# kinks.net
KiCad netlist of a schematic drawn in EAGLE
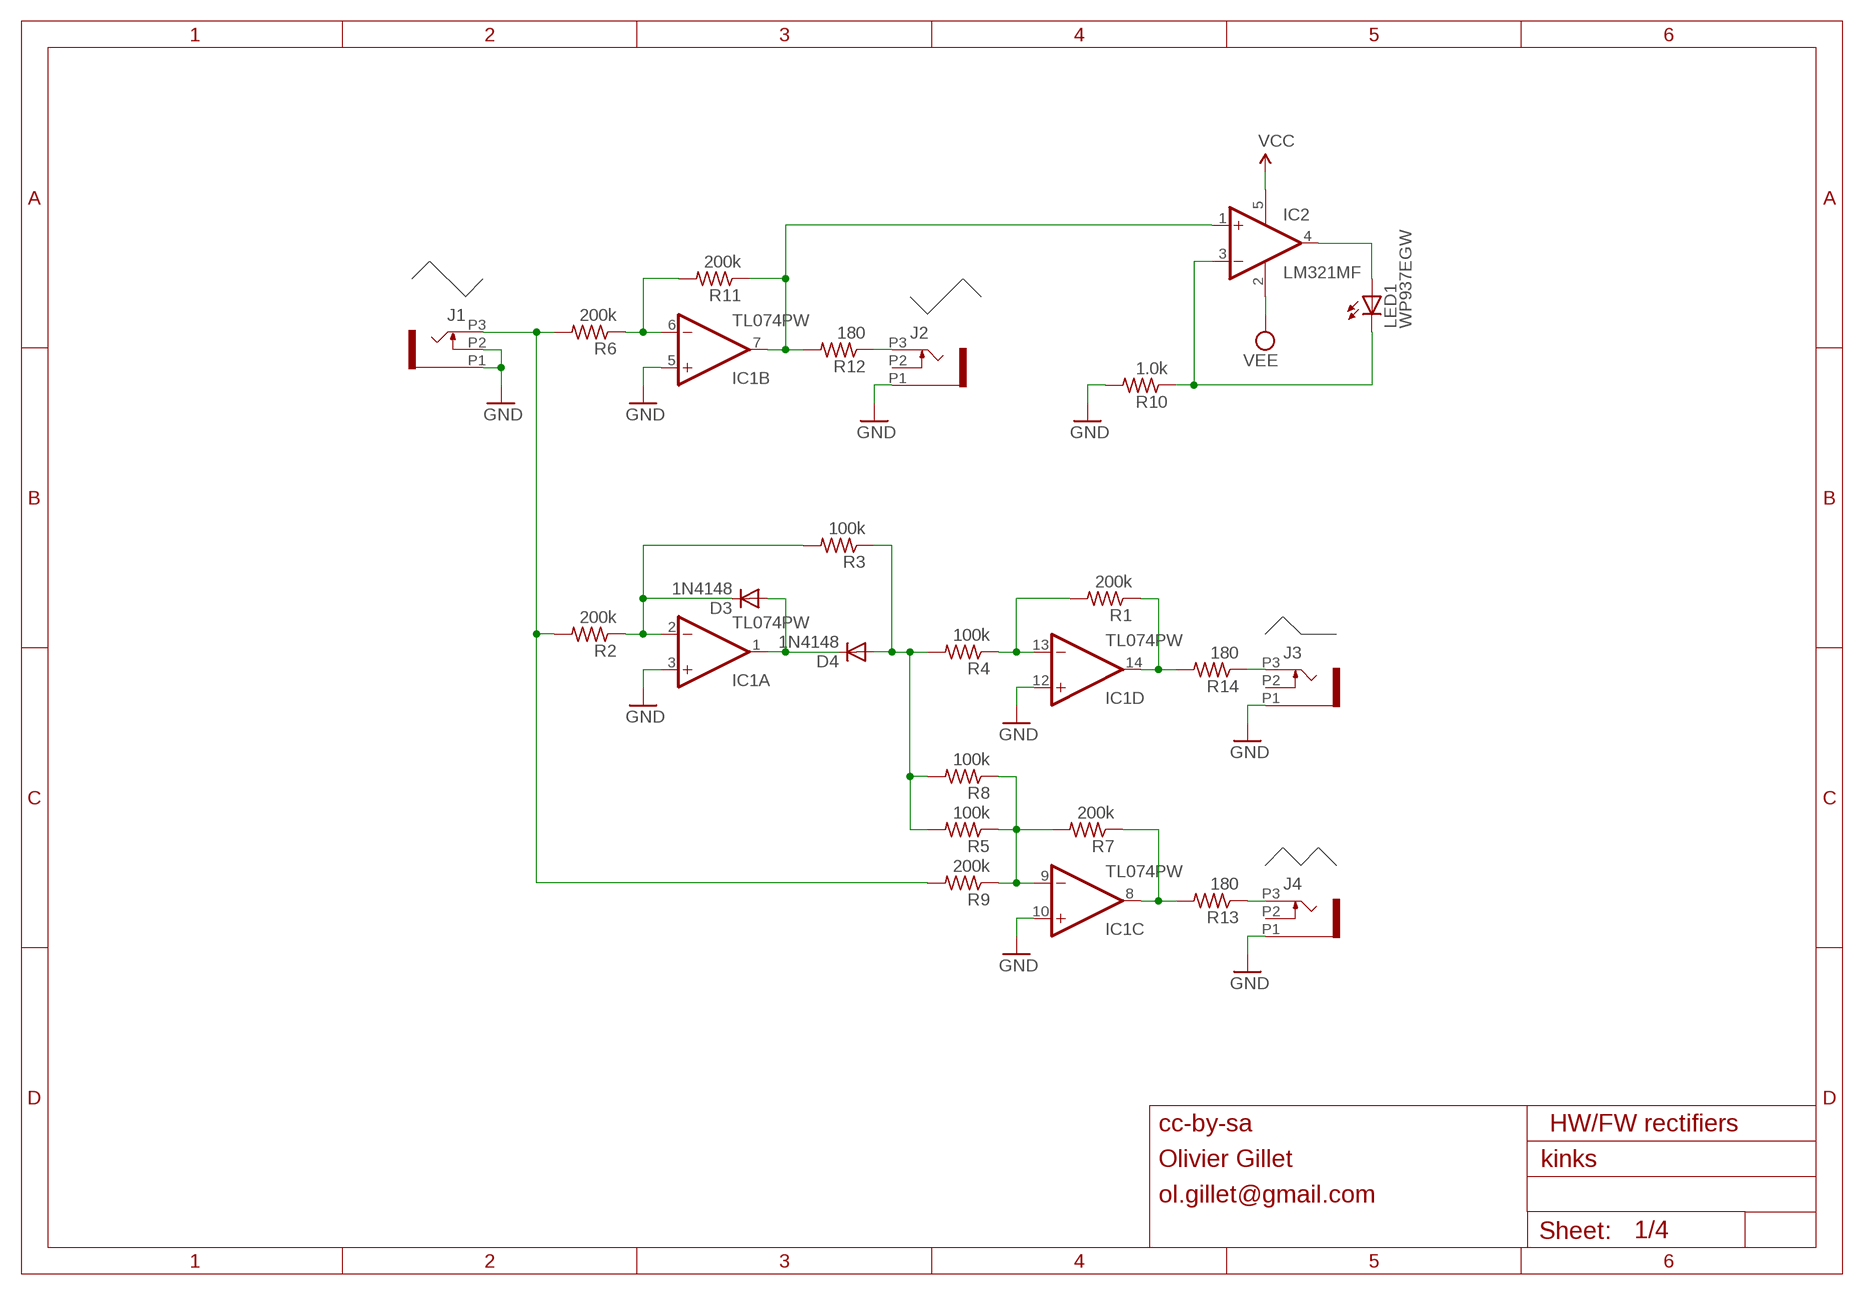
[diagram p0: schematic, sheet 1]
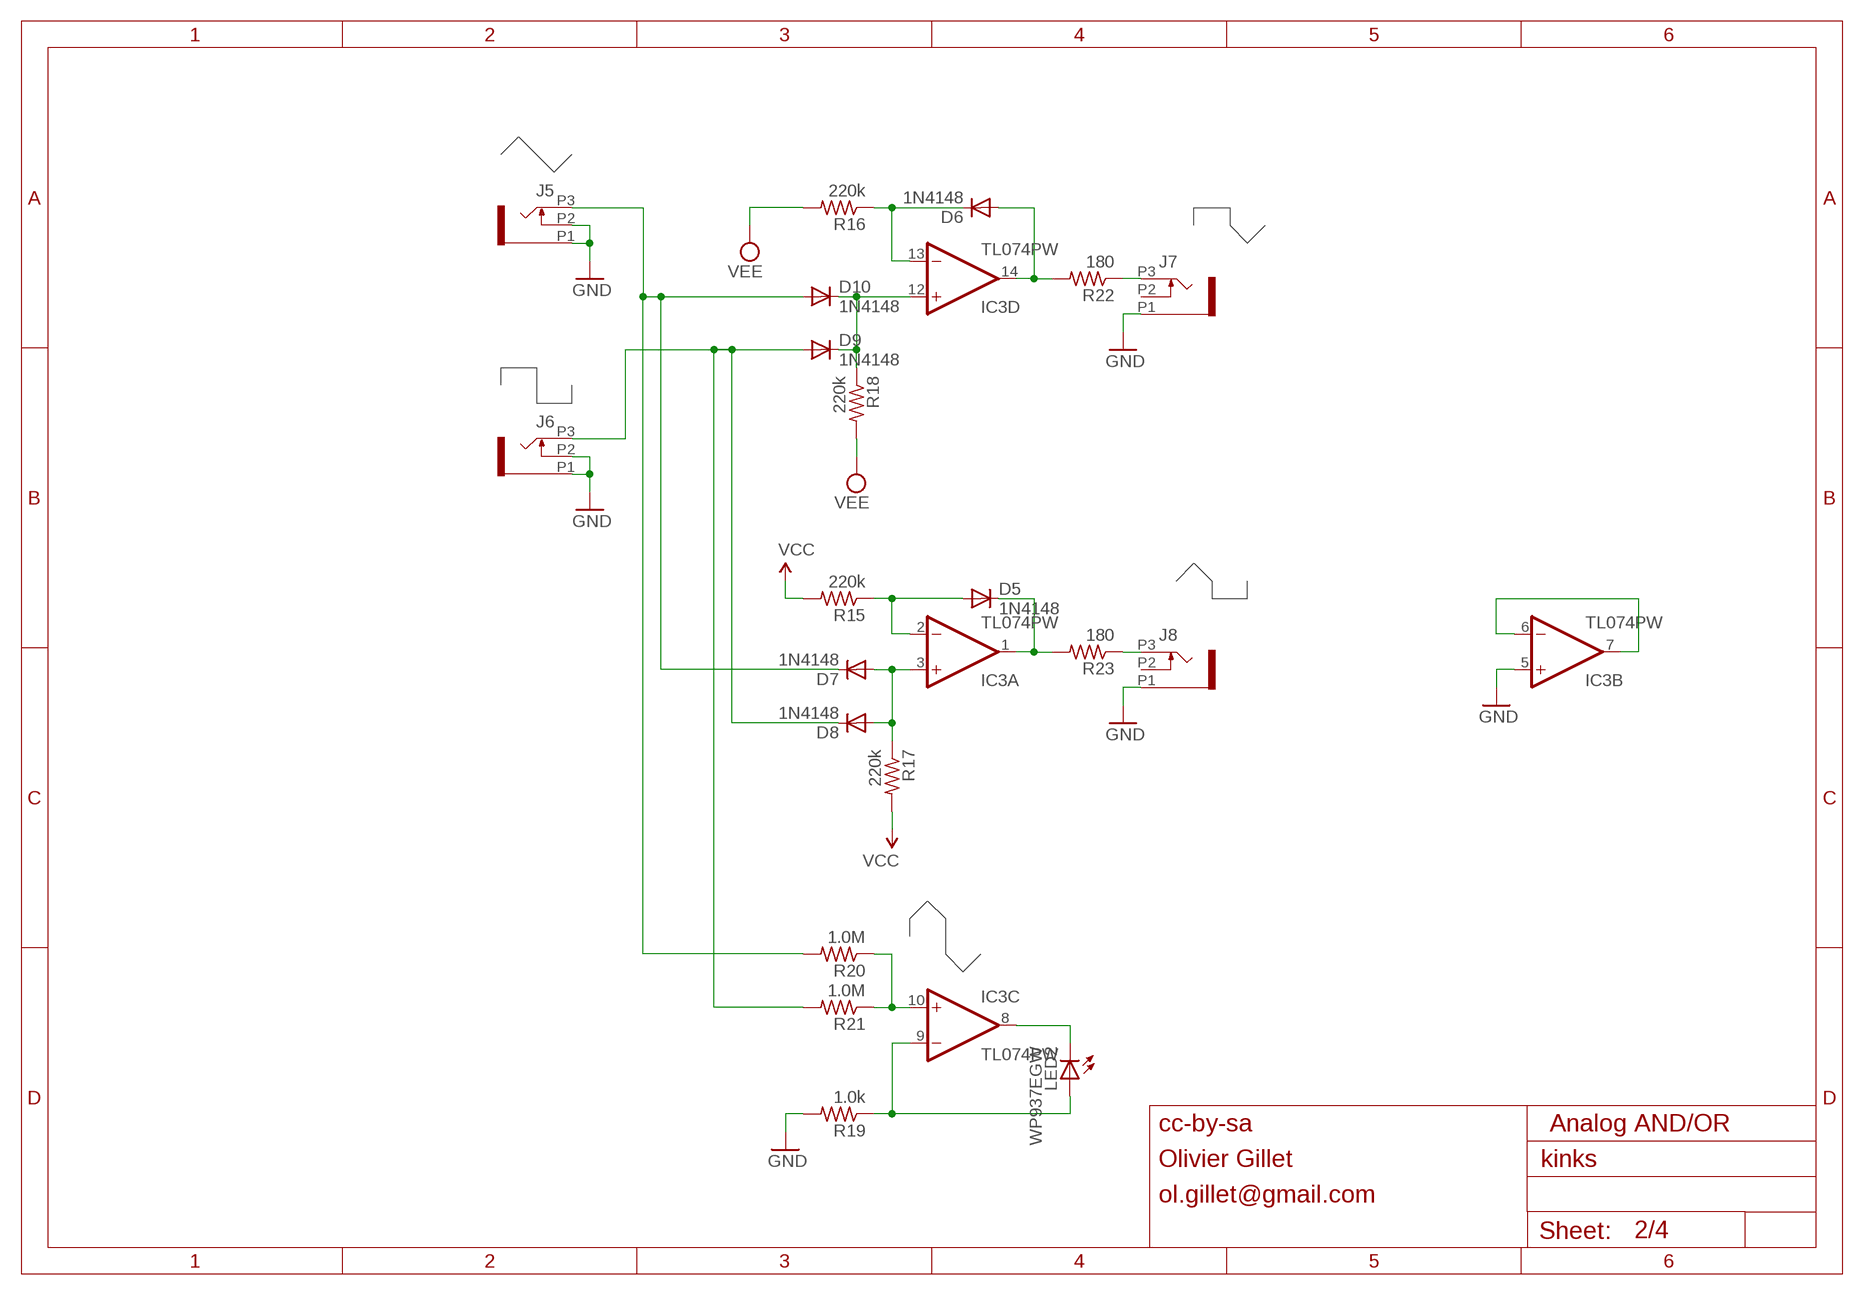
[diagram p1: schematic, sheet 2]
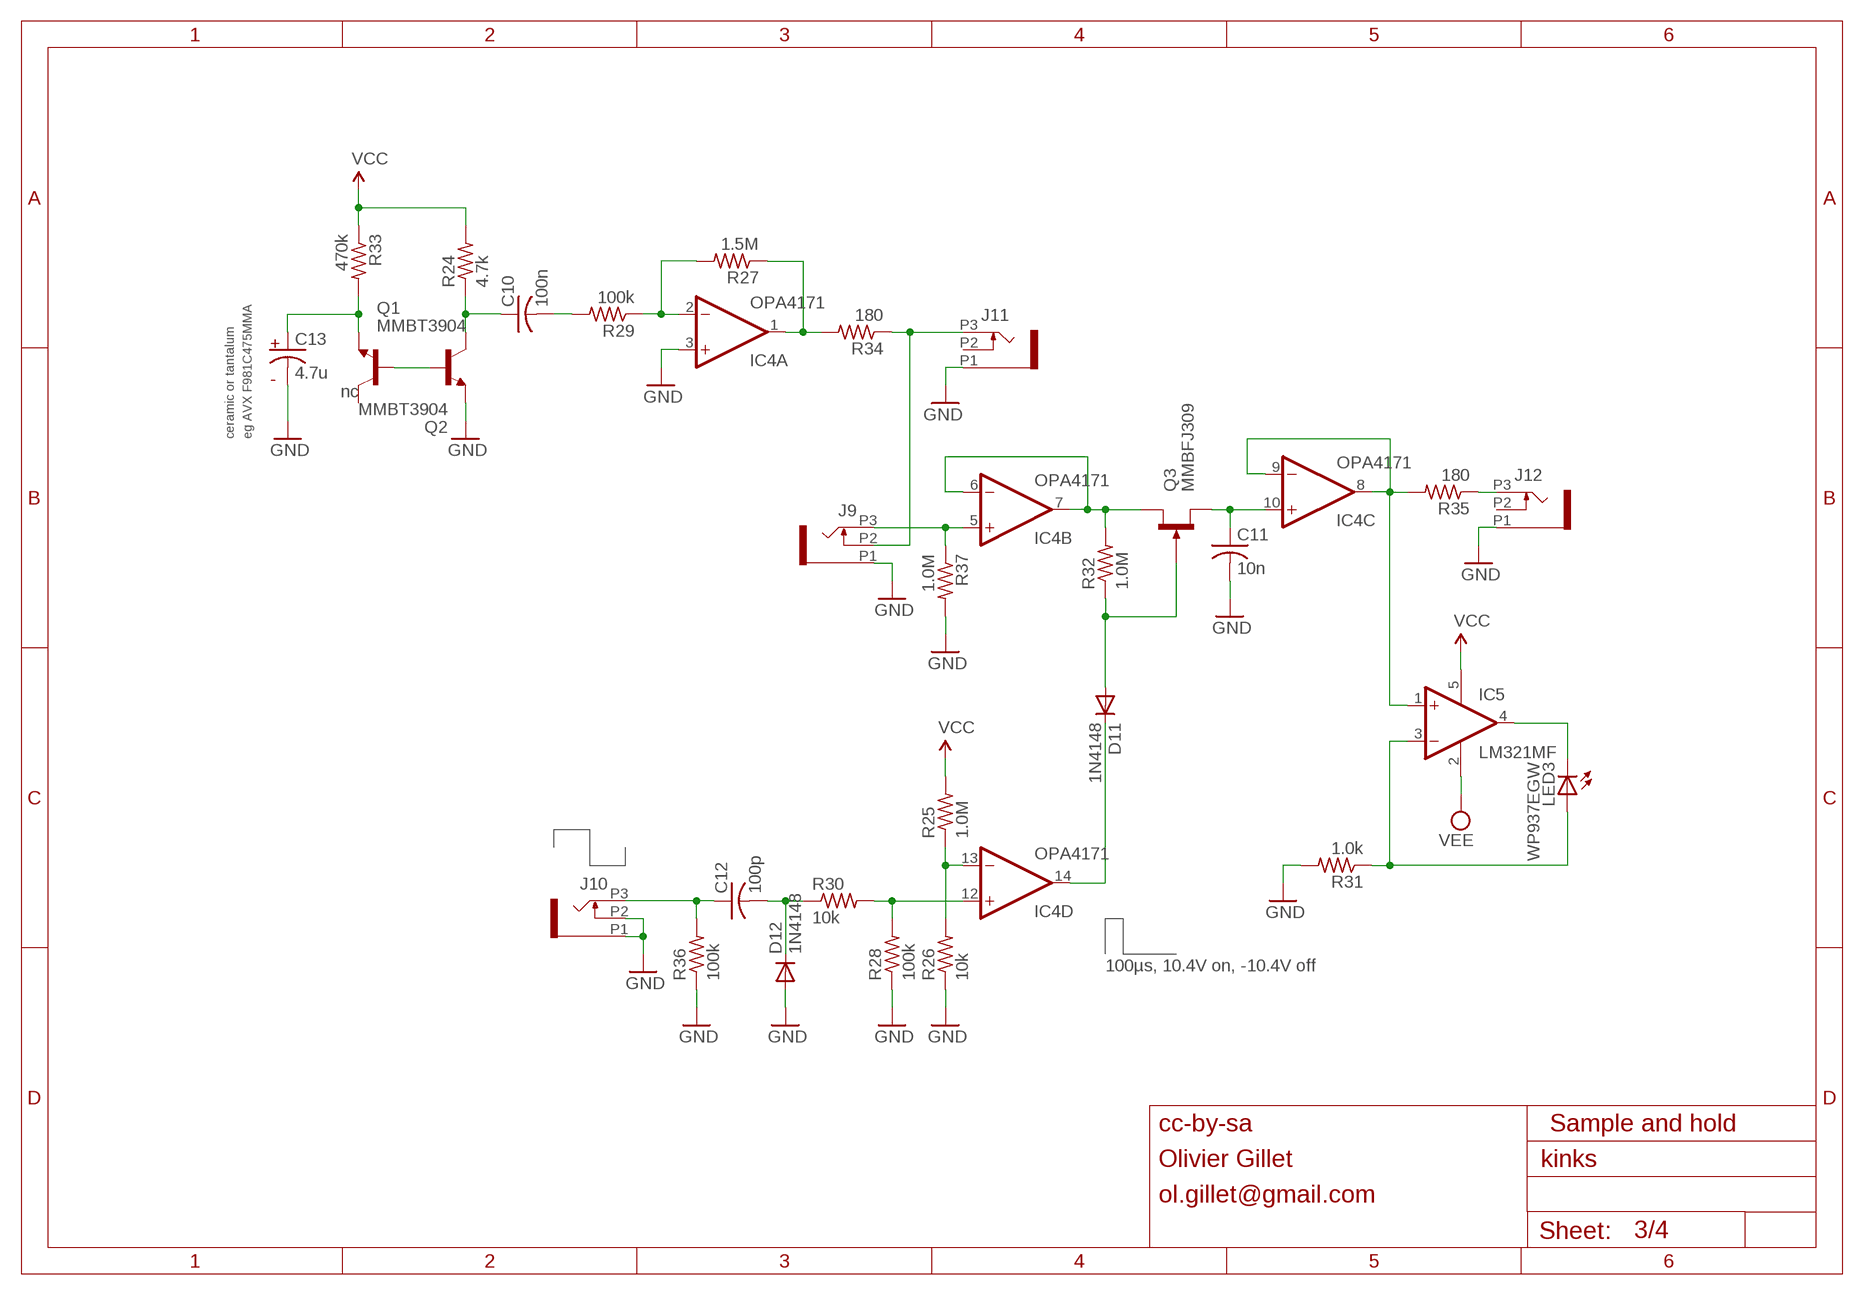
[diagram p2: schematic, sheet 3]
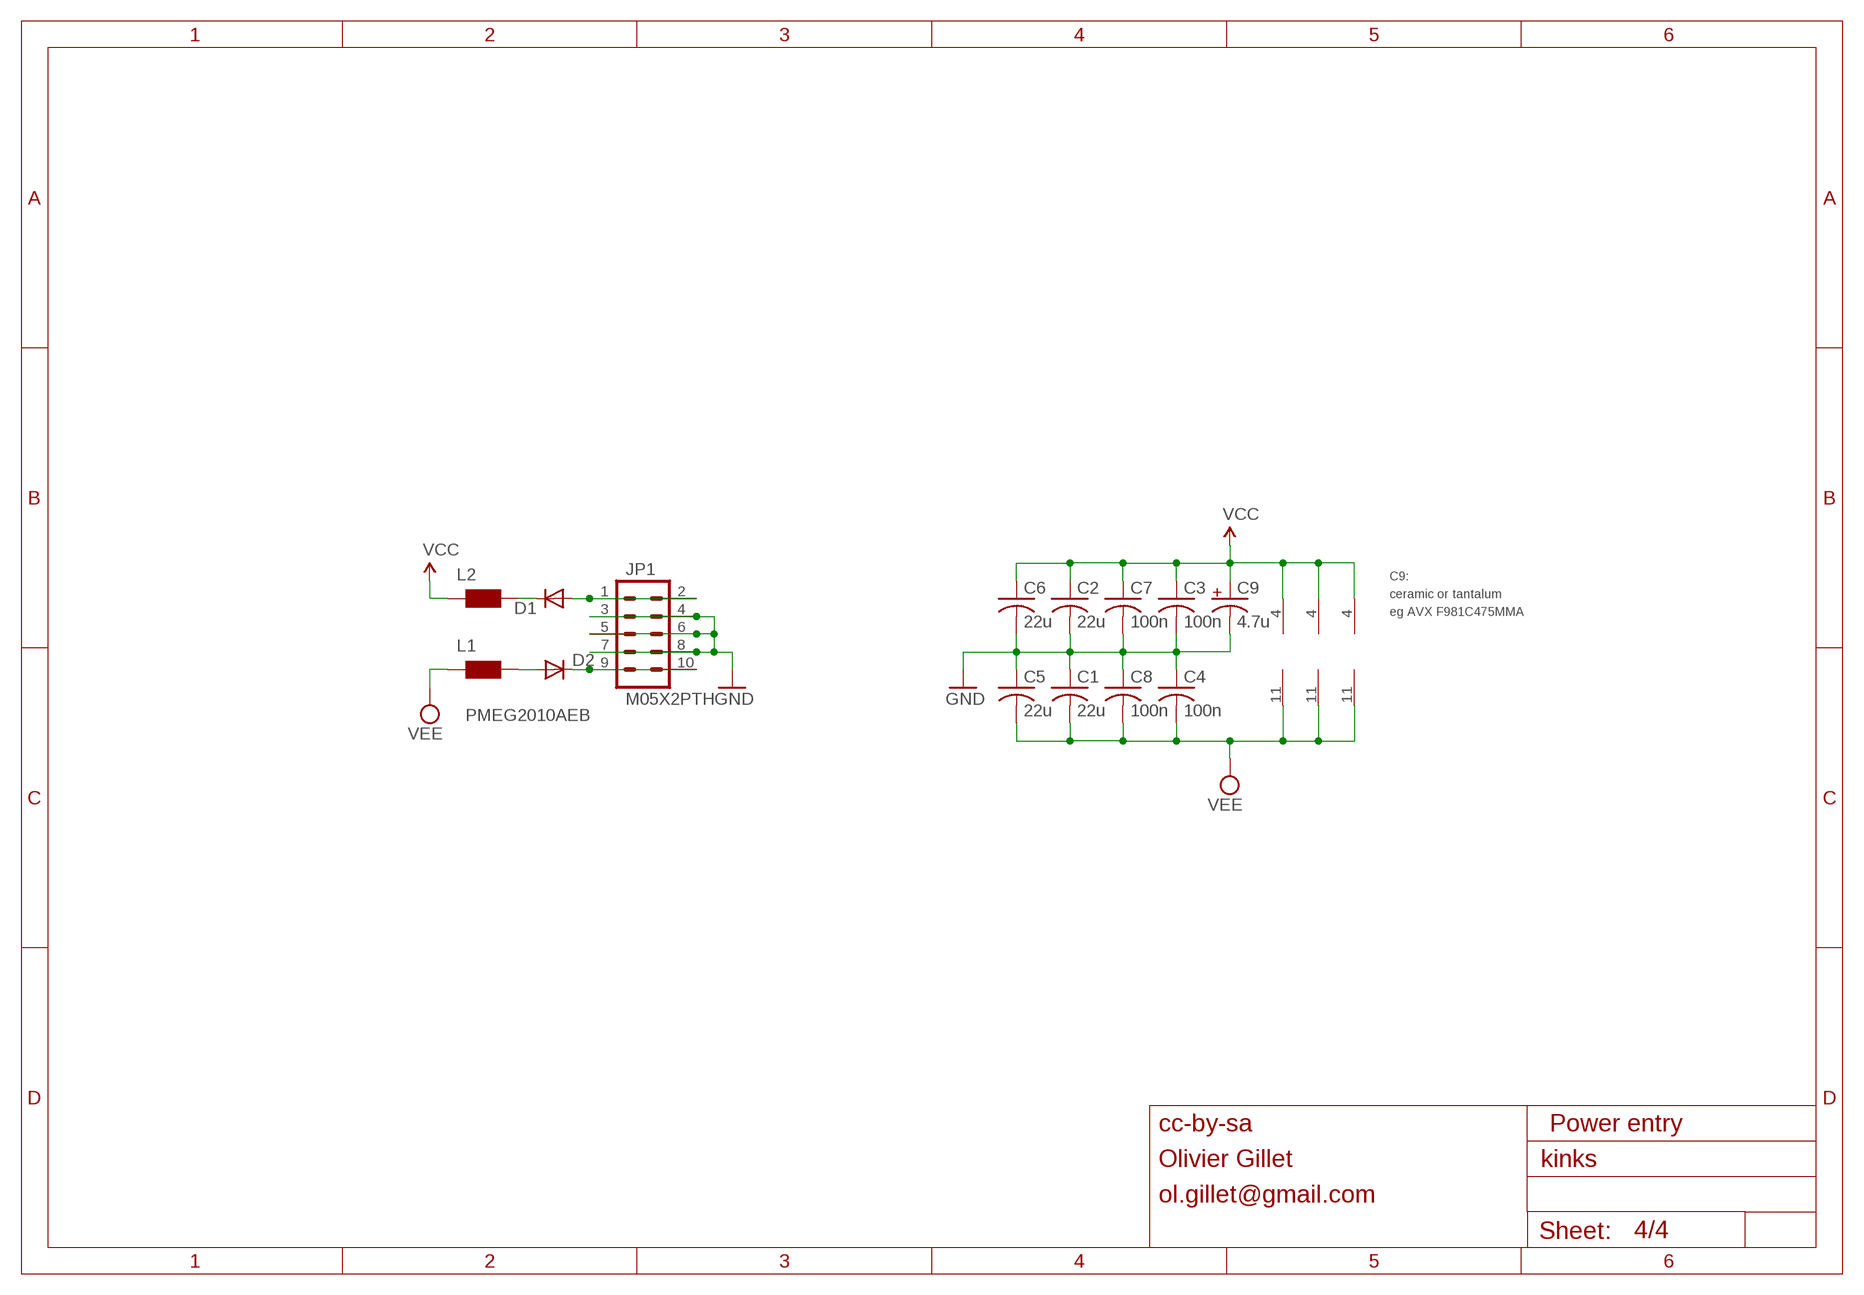
[diagram p3: schematic, sheet 4]

(export (version "E")
  (design (tool "Eeschema 10.0.6"))
  (components
    (comp (ref "D3")
      (value "1N4148")
      (footprint "eagle-import:SOD523")
      (libsource (lib "eagle-import") (part "DIODE-SOD523"))
    )
    (comp (ref "D4")
      (value "1N4148")
      (footprint "eagle-import:SOD523")
      (libsource (lib "eagle-import") (part "DIODE-SOD523"))
    )
    (comp (ref "IC1")
      (value "TL074PW")
      (footprint "eagle-import:TSSOP14")
      (libsource (lib "eagle-import") (part "TL074PW"))
    )
    (comp (ref "IC2")
      (value "LM321MF")
      (footprint "eagle-import:SOT23-5")
      (libsource (lib "eagle-import") (part "LM321?MF"))
    )
    (comp (ref "J1")
      (value "PJ301_THONKICONN6")
      (footprint "eagle-import:WQP_PJ_301M6")
      (libsource (lib "eagle-import") (part "PJ301_THONKICONN6"))
    )
    (comp (ref "J2")
      (value "PJ301_THONKICONN6")
      (footprint "eagle-import:WQP_PJ_301M6")
      (libsource (lib "eagle-import") (part "PJ301_THONKICONN6"))
    )
    (comp (ref "J3")
      (value "PJ301_THONKICONN6")
      (footprint "eagle-import:WQP_PJ_301M6")
      (libsource (lib "eagle-import") (part "PJ301_THONKICONN6"))
    )
    (comp (ref "J4")
      (value "PJ301_THONKICONN6")
      (footprint "eagle-import:WQP_PJ_301M6")
      (libsource (lib "eagle-import") (part "PJ301_THONKICONN6"))
    )
    (comp (ref "LED1")
      (value "WP937EGW")
      (footprint "eagle-import:LED3MM")
      (libsource (lib "eagle-import") (part "LED3MM"))
    )
    (comp (ref "R1")
      (value "200k")
      (footprint "eagle-import:R0402")
      (libsource (lib "eagle-import") (part "R-US_R0402"))
    )
    (comp (ref "R2")
      (value "200k")
      (footprint "eagle-import:R0402")
      (libsource (lib "eagle-import") (part "R-US_R0402"))
    )
    (comp (ref "R3")
      (value "100k")
      (footprint "eagle-import:R0402")
      (libsource (lib "eagle-import") (part "R-US_R0402"))
    )
    (comp (ref "R4")
      (value "100k")
      (footprint "eagle-import:R0402")
      (libsource (lib "eagle-import") (part "R-US_R0402"))
    )
    (comp (ref "R5")
      (value "100k")
      (footprint "eagle-import:R0402")
      (libsource (lib "eagle-import") (part "R-US_R0402"))
    )
    (comp (ref "R6")
      (value "200k")
      (footprint "eagle-import:R0402")
      (libsource (lib "eagle-import") (part "R-US_R0402"))
    )
    (comp (ref "R7")
      (value "200k")
      (footprint "eagle-import:R0402")
      (libsource (lib "eagle-import") (part "R-US_R0402"))
    )
    (comp (ref "R8")
      (value "100k")
      (footprint "eagle-import:R0402")
      (libsource (lib "eagle-import") (part "R-US_R0402"))
    )
    (comp (ref "R9")
      (value "200k")
      (footprint "eagle-import:R0402")
      (libsource (lib "eagle-import") (part "R-US_R0402"))
    )
    (comp (ref "R10")
      (value "1.0k")
      (footprint "eagle-import:R0402")
      (libsource (lib "eagle-import") (part "R-US_R0402"))
    )
    (comp (ref "R11")
      (value "200k")
      (footprint "eagle-import:R0402")
      (libsource (lib "eagle-import") (part "R-US_R0402"))
    )
    (comp (ref "R12")
      (value "180")
      (footprint "eagle-import:R0402")
      (libsource (lib "eagle-import") (part "R-US_R0402"))
    )
    (comp (ref "R13")
      (value "180")
      (footprint "eagle-import:R0402")
      (libsource (lib "eagle-import") (part "R-US_R0402"))
    )
    (comp (ref "R14")
      (value "180")
      (footprint "eagle-import:R0402")
      (libsource (lib "eagle-import") (part "R-US_R0402"))
    )
    (comp (ref "D5")
      (value "1N4148")
      (footprint "eagle-import:SOD523")
      (libsource (lib "eagle-import") (part "DIODE-SOD523"))
    )
    (comp (ref "D6")
      (value "1N4148")
      (footprint "eagle-import:SOD523")
      (libsource (lib "eagle-import") (part "DIODE-SOD523"))
    )
    (comp (ref "D7")
      (value "1N4148")
      (footprint "eagle-import:SOD523")
      (libsource (lib "eagle-import") (part "DIODE-SOD523"))
    )
    (comp (ref "D8")
      (value "1N4148")
      (footprint "eagle-import:SOD523")
      (libsource (lib "eagle-import") (part "DIODE-SOD523"))
    )
    (comp (ref "D9")
      (value "1N4148")
      (footprint "eagle-import:SOD523")
      (libsource (lib "eagle-import") (part "DIODE-SOD523"))
    )
    (comp (ref "D10")
      (value "1N4148")
      (footprint "eagle-import:SOD523")
      (libsource (lib "eagle-import") (part "DIODE-SOD523"))
    )
    (comp (ref "IC3")
      (value "TL074PW")
      (footprint "eagle-import:TSSOP14")
      (libsource (lib "eagle-import") (part "TL074PW"))
    )
    (comp (ref "J5")
      (value "PJ301_THONKICONN6")
      (footprint "eagle-import:WQP_PJ_301M6")
      (libsource (lib "eagle-import") (part "PJ301_THONKICONN6"))
    )
    (comp (ref "J6")
      (value "PJ301_THONKICONN6")
      (footprint "eagle-import:WQP_PJ_301M6")
      (libsource (lib "eagle-import") (part "PJ301_THONKICONN6"))
    )
    (comp (ref "J7")
      (value "PJ301_THONKICONN6")
      (footprint "eagle-import:WQP_PJ_301M6")
      (libsource (lib "eagle-import") (part "PJ301_THONKICONN6"))
    )
    (comp (ref "J8")
      (value "PJ301_THONKICONN6")
      (footprint "eagle-import:WQP_PJ_301M6")
      (libsource (lib "eagle-import") (part "PJ301_THONKICONN6"))
    )
    (comp (ref "LED2")
      (value "WP937EGW")
      (footprint "eagle-import:LED3MM")
      (libsource (lib "eagle-import") (part "LED3MM"))
    )
    (comp (ref "R15")
      (value "220k")
      (footprint "eagle-import:R0402")
      (libsource (lib "eagle-import") (part "R-US_R0402"))
    )
    (comp (ref "R16")
      (value "220k")
      (footprint "eagle-import:R0402")
      (libsource (lib "eagle-import") (part "R-US_R0402"))
    )
    (comp (ref "R17")
      (value "220k")
      (footprint "eagle-import:R0402")
      (libsource (lib "eagle-import") (part "R-US_R0402"))
    )
    (comp (ref "R18")
      (value "220k")
      (footprint "eagle-import:R0402")
      (libsource (lib "eagle-import") (part "R-US_R0402"))
    )
    (comp (ref "R19")
      (value "1.0k")
      (footprint "eagle-import:R0402")
      (libsource (lib "eagle-import") (part "R-US_R0402"))
    )
    (comp (ref "R20")
      (value "1.0M")
      (footprint "eagle-import:R0402")
      (libsource (lib "eagle-import") (part "R-US_R0402"))
    )
    (comp (ref "R21")
      (value "1.0M")
      (footprint "eagle-import:R0402")
      (libsource (lib "eagle-import") (part "R-US_R0402"))
    )
    (comp (ref "R22")
      (value "180")
      (footprint "eagle-import:R0402")
      (libsource (lib "eagle-import") (part "R-US_R0402"))
    )
    (comp (ref "R23")
      (value "180")
      (footprint "eagle-import:R0402")
      (libsource (lib "eagle-import") (part "R-US_R0402"))
    )
    (comp (ref "C10")
      (value "100n")
      (footprint "eagle-import:C0402")
      (libsource (lib "eagle-import") (part "C-USC0402"))
    )
    (comp (ref "C11")
      (value "10n")
      (footprint "eagle-import:C0603")
      (libsource (lib "eagle-import") (part "C-USC0603"))
    )
    (comp (ref "C12")
      (value "100p")
      (footprint "eagle-import:C0402")
      (libsource (lib "eagle-import") (part "C-USC0402"))
    )
    (comp (ref "C13")
      (value "4.7u")
      (footprint "eagle-import:C0603")
      (libsource (lib "eagle-import") (part "C-USC0603"))
    )
    (comp (ref "D11")
      (value "1N4148")
      (footprint "eagle-import:SOD523")
      (libsource (lib "eagle-import") (part "DIODE-SOD523"))
    )
    (comp (ref "D12")
      (value "1N4148")
      (footprint "eagle-import:SOD523")
      (libsource (lib "eagle-import") (part "DIODE-SOD523"))
    )
    (comp (ref "IC4")
      (value "OPA4171")
      (footprint "eagle-import:TSSOP14")
      (libsource (lib "eagle-import") (part "TL074PW"))
    )
    (comp (ref "IC5")
      (value "LM321MF")
      (footprint "eagle-import:SOT23-5")
      (libsource (lib "eagle-import") (part "LM321?MF"))
    )
    (comp (ref "J9")
      (value "PJ301_THONKICONN6")
      (footprint "eagle-import:WQP_PJ_301M6")
      (libsource (lib "eagle-import") (part "PJ301_THONKICONN6"))
    )
    (comp (ref "J10")
      (value "PJ301_THONKICONN6")
      (footprint "eagle-import:WQP_PJ_301M6")
      (libsource (lib "eagle-import") (part "PJ301_THONKICONN6"))
    )
    (comp (ref "J11")
      (value "PJ301_THONKICONN6")
      (footprint "eagle-import:WQP_PJ_301M6")
      (libsource (lib "eagle-import") (part "PJ301_THONKICONN6"))
    )
    (comp (ref "J12")
      (value "PJ301_THONKICONN6")
      (footprint "eagle-import:WQP_PJ_301M6")
      (libsource (lib "eagle-import") (part "PJ301_THONKICONN6"))
    )
    (comp (ref "LED3")
      (value "WP937EGW")
      (footprint "eagle-import:LED3MM")
      (libsource (lib "eagle-import") (part "LED3MM"))
    )
    (comp (ref "Q1")
      (value "MMBT3904")
      (footprint "eagle-import:SOT23-BEC")
      (libsource (lib "eagle-import") (part "-NPN-SOT23-BECMMBT3904LT1"))
    )
    (comp (ref "Q2")
      (value "MMBT3904")
      (footprint "eagle-import:SOT23-BEC")
      (libsource (lib "eagle-import") (part "-NPN-SOT23-BECMMBT3904LT1"))
    )
    (comp (ref "Q3")
      (value "MMBFJ309")
      (footprint "eagle-import:SOT23")
      (libsource (lib "eagle-import") (part "MMBFJ3"))
    )
    (comp (ref "R24")
      (value "4.7k")
      (footprint "eagle-import:R0402")
      (libsource (lib "eagle-import") (part "R-US_R0402"))
    )
    (comp (ref "R25")
      (value "1.0M")
      (footprint "eagle-import:R0402")
      (libsource (lib "eagle-import") (part "R-US_R0402"))
    )
    (comp (ref "R26")
      (value "10k")
      (footprint "eagle-import:R0402")
      (libsource (lib "eagle-import") (part "R-US_R0402"))
    )
    (comp (ref "R27")
      (value "1.5M")
      (footprint "eagle-import:R0402")
      (libsource (lib "eagle-import") (part "R-US_R0402"))
    )
    (comp (ref "R28")
      (value "100k")
      (footprint "eagle-import:R0402")
      (libsource (lib "eagle-import") (part "R-US_R0402"))
    )
    (comp (ref "R29")
      (value "100k")
      (footprint "eagle-import:R0402")
      (libsource (lib "eagle-import") (part "R-US_R0402"))
    )
    (comp (ref "R30")
      (value "10k")
      (footprint "eagle-import:R0402")
      (libsource (lib "eagle-import") (part "R-US_R0402"))
    )
    (comp (ref "R31")
      (value "1.0k")
      (footprint "eagle-import:R0402")
      (libsource (lib "eagle-import") (part "R-US_R0402"))
    )
    (comp (ref "R32")
      (value "1.0M")
      (footprint "eagle-import:R0402")
      (libsource (lib "eagle-import") (part "R-US_R0402"))
    )
    (comp (ref "R33")
      (value "470k")
      (footprint "eagle-import:R0402")
      (libsource (lib "eagle-import") (part "R-US_R0402"))
    )
    (comp (ref "R34")
      (value "180")
      (footprint "eagle-import:R0402")
      (libsource (lib "eagle-import") (part "R-US_R0402"))
    )
    (comp (ref "R35")
      (value "180")
      (footprint "eagle-import:R0402")
      (libsource (lib "eagle-import") (part "R-US_R0402"))
    )
    (comp (ref "R36")
      (value "100k")
      (footprint "eagle-import:R0402")
      (libsource (lib "eagle-import") (part "R-US_R0402"))
    )
    (comp (ref "R37")
      (value "1.0M")
      (footprint "eagle-import:R0402")
      (libsource (lib "eagle-import") (part "R-US_R0402"))
    )
    (comp (ref "C1")
      (value "22u")
      (footprint "eagle-import:C0805")
      (libsource (lib "eagle-import") (part "C-USC0805"))
    )
    (comp (ref "C2")
      (value "22u")
      (footprint "eagle-import:C0805")
      (libsource (lib "eagle-import") (part "C-USC0805"))
    )
    (comp (ref "C3")
      (value "100n")
      (footprint "eagle-import:C0402")
      (libsource (lib "eagle-import") (part "C-USC0402"))
    )
    (comp (ref "C4")
      (value "100n")
      (footprint "eagle-import:C0402")
      (libsource (lib "eagle-import") (part "C-USC0402"))
    )
    (comp (ref "C5")
      (value "22u")
      (footprint "eagle-import:C0805")
      (libsource (lib "eagle-import") (part "C-USC0805"))
    )
    (comp (ref "C6")
      (value "22u")
      (footprint "eagle-import:C0805")
      (libsource (lib "eagle-import") (part "C-USC0805"))
    )
    (comp (ref "C7")
      (value "100n")
      (footprint "eagle-import:C0402")
      (libsource (lib "eagle-import") (part "C-USC0402"))
    )
    (comp (ref "C8")
      (value "100n")
      (footprint "eagle-import:C0402")
      (libsource (lib "eagle-import") (part "C-USC0402"))
    )
    (comp (ref "C9")
      (value "4.7u")
      (footprint "eagle-import:C0603")
      (libsource (lib "eagle-import") (part "C-USC0603"))
    )
    (comp (ref "D1")
      (value "PMEG2010AEB")
      (footprint "eagle-import:SOD523")
      (libsource (lib "eagle-import") (part "DIODE-SOD523"))
    )
    (comp (ref "D2")
      (value "PMEG2010AEB")
      (footprint "eagle-import:SOD523")
      (libsource (lib "eagle-import") (part "DIODE-SOD523"))
    )
    (comp (ref "JP1")
      (value "M05X2PTH")
      (footprint "eagle-import:AVR_ICSP")
      (libsource (lib "eagle-import") (part "M05X2PTH"))
    )
    (comp (ref "L1")
      (value "WE-CBF_0603")
      (footprint "eagle-import:0603")
      (libsource (lib "eagle-import") (part "WE-CBF_0603"))
    )
    (comp (ref "L2")
      (value "WE-CBF_0603")
      (footprint "eagle-import:0603")
      (libsource (lib "eagle-import") (part "WE-CBF_0603"))
    )
  )
  (nets
    (net (code "1") (name "GND") (class "Default")
      (node (ref "C1") (pin "1") (pinfunction "1_1") (pintype "passive"))
      (node (ref "C11") (pin "2") (pinfunction "2_2") (pintype "passive"))
      (node (ref "C13") (pin "2") (pinfunction "2_2") (pintype "passive"))
      (node (ref "C2") (pin "2") (pinfunction "2_2") (pintype "passive"))
      (node (ref "C3") (pin "2") (pinfunction "2_2") (pintype "passive"))
      (node (ref "C4") (pin "1") (pinfunction "1_1") (pintype "passive"))
      (node (ref "C5") (pin "1") (pinfunction "1_1") (pintype "passive"))
      (node (ref "C6") (pin "2") (pinfunction "2_2") (pintype "passive"))
      (node (ref "C7") (pin "2") (pinfunction "2_2") (pintype "passive"))
      (node (ref "C8") (pin "1") (pinfunction "1_1") (pintype "passive"))
      (node (ref "C9") (pin "2") (pinfunction "2_2") (pintype "passive"))
      (node (ref "D12") (pin "A") (pinfunction "A_A") (pintype "passive"))
      (node (ref "IC1") (pin "10") (pinfunction "+IN_10") (pintype "input"))
      (node (ref "IC1") (pin "12") (pinfunction "+IN_12") (pintype "input"))
      (node (ref "IC1") (pin "3") (pinfunction "+IN_3") (pintype "input"))
      (node (ref "IC1") (pin "5") (pinfunction "+IN_5") (pintype "input"))
      (node (ref "IC3") (pin "5") (pinfunction "+IN_5") (pintype "input"))
      (node (ref "IC4") (pin "3") (pinfunction "+IN_3") (pintype "input"))
      (node (ref "J1") (pin "P1") (pinfunction "1_P1") (pintype "passive"))
      (node (ref "J1") (pin "P2") (pinfunction "2_P2") (pintype "passive"))
      (node (ref "J10") (pin "P1") (pinfunction "1_P1") (pintype "passive"))
      (node (ref "J10") (pin "P2") (pinfunction "2_P2") (pintype "passive"))
      (node (ref "J11") (pin "P1") (pinfunction "1_P1") (pintype "passive"))
      (node (ref "J12") (pin "P1") (pinfunction "1_P1") (pintype "passive"))
      (node (ref "J2") (pin "P1") (pinfunction "1_P1") (pintype "passive"))
      (node (ref "J3") (pin "P1") (pinfunction "1_P1") (pintype "passive"))
      (node (ref "J4") (pin "P1") (pinfunction "1_P1") (pintype "passive"))
      (node (ref "J5") (pin "P1") (pinfunction "1_P1") (pintype "passive"))
      (node (ref "J5") (pin "P2") (pinfunction "2_P2") (pintype "passive"))
      (node (ref "J6") (pin "P1") (pinfunction "1_P1") (pintype "passive"))
      (node (ref "J6") (pin "P2") (pinfunction "2_P2") (pintype "passive"))
      (node (ref "J7") (pin "P1") (pinfunction "1_P1") (pintype "passive"))
      (node (ref "J8") (pin "P1") (pinfunction "1_P1") (pintype "passive"))
      (node (ref "J9") (pin "P1") (pinfunction "1_P1") (pintype "passive"))
      (node (ref "JP1") (pin "3") (pinfunction "3_3") (pintype "passive"))
      (node (ref "JP1") (pin "4") (pinfunction "4_4") (pintype "passive"))
      (node (ref "JP1") (pin "5") (pinfunction "5_5") (pintype "passive"))
      (node (ref "JP1") (pin "6") (pinfunction "6_6") (pintype "passive"))
      (node (ref "JP1") (pin "7") (pinfunction "7_7") (pintype "passive"))
      (node (ref "JP1") (pin "8") (pinfunction "8_8") (pintype "passive"))
      (node (ref "Q1") (pin "E") (pinfunction "E_E") (pintype "passive"))
      (node (ref "R10") (pin "2") (pinfunction "2_2") (pintype "passive"))
      (node (ref "R19") (pin "2") (pinfunction "2_2") (pintype "passive"))
      (node (ref "R26") (pin "1") (pinfunction "1_1") (pintype "passive"))
      (node (ref "R28") (pin "1") (pinfunction "1_1") (pintype "passive"))
      (node (ref "R31") (pin "2") (pinfunction "2_2") (pintype "passive"))
      (node (ref "R36") (pin "1") (pinfunction "1_1") (pintype "passive"))
      (node (ref "R37") (pin "2") (pinfunction "2_2") (pintype "passive"))
    )
    (net (code "2") (name "Net-(C10-Pad1)") (class "Default")
      (node (ref "C10") (pin "1") (pinfunction "1_1") (pintype "passive"))
      (node (ref "Q1") (pin "C") (pinfunction "C_C") (pintype "passive"))
      (node (ref "R24") (pin "1") (pinfunction "1_1") (pintype "passive"))
    )
    (net (code "3") (name "Net-(C10-Pad2)") (class "Default")
      (node (ref "C10") (pin "2") (pinfunction "2_2") (pintype "passive"))
      (node (ref "R29") (pin "2") (pinfunction "2_2") (pintype "passive"))
    )
    (net (code "4") (name "Net-(C12-Pad2)") (class "Default")
      (node (ref "C12") (pin "2") (pinfunction "2_2") (pintype "passive"))
      (node (ref "D12") (pin "C") (pinfunction "C_C") (pintype "passive"))
      (node (ref "R30") (pin "1") (pinfunction "1_1") (pintype "passive"))
    )
    (net (code "5") (name "Net-(C13-Pad1)") (class "Default")
      (node (ref "C13") (pin "1") (pinfunction "1_1") (pintype "passive"))
      (node (ref "Q2") (pin "E") (pinfunction "E_E") (pintype "passive"))
      (node (ref "R33") (pin "2") (pinfunction "2_2") (pintype "passive"))
    )
    (net (code "6") (name "Net-(D1-PadA)") (class "Default")
      (node (ref "D1") (pin "A") (pinfunction "A_A") (pintype "passive"))
      (node (ref "JP1") (pin "1") (pinfunction "1_1") (pintype "passive"))
      (node (ref "JP1") (pin "2") (pinfunction "2_2") (pintype "passive"))
    )
    (net (code "7") (name "Net-(D1-PadC)") (class "Default")
      (node (ref "D1") (pin "C") (pinfunction "C_C") (pintype "passive"))
      (node (ref "L2") (pin "2") (pinfunction "2_2") (pintype "passive"))
    )
    (net (code "8") (name "Net-(D2-PadA)") (class "Default")
      (node (ref "D2") (pin "A") (pinfunction "A_A") (pintype "passive"))
      (node (ref "L1") (pin "2") (pinfunction "2_2") (pintype "passive"))
    )
    (net (code "9") (name "Net-(D2-PadC)") (class "Default")
      (node (ref "D2") (pin "C") (pinfunction "C_C") (pintype "passive"))
      (node (ref "JP1") (pin "10") (pinfunction "10_10") (pintype "passive"))
      (node (ref "JP1") (pin "9") (pinfunction "9_9") (pintype "passive"))
    )
    (net (code "10") (name "Net-(D4-PadA)") (class "Default")
      (node (ref "D4") (pin "A") (pinfunction "A_A") (pintype "passive"))
      (node (ref "R3") (pin "1") (pinfunction "1_1") (pintype "passive"))
      (node (ref "R4") (pin "2") (pinfunction "2_2") (pintype "passive"))
      (node (ref "R5") (pin "2") (pinfunction "2_2") (pintype "passive"))
      (node (ref "R8") (pin "2") (pinfunction "2_2") (pintype "passive"))
    )
    (net (code "11") (name "Net-(IC1A--IN)") (class "Default")
      (node (ref "D3") (pin "C") (pinfunction "C_C") (pintype "passive"))
      (node (ref "IC1") (pin "2") (pinfunction "-IN_2") (pintype "input"))
      (node (ref "R2") (pin "1") (pinfunction "1_1") (pintype "passive"))
      (node (ref "R3") (pin "2") (pinfunction "2_2") (pintype "passive"))
    )
    (net (code "12") (name "Net-(IC1A-OUT)") (class "Default")
      (node (ref "D3") (pin "A") (pinfunction "A_A") (pintype "passive"))
      (node (ref "D4") (pin "C") (pinfunction "C_C") (pintype "passive"))
      (node (ref "IC1") (pin "1") (pinfunction "OUT_1") (pintype "output"))
    )
    (net (code "13") (name "Net-(IC1B--IN)") (class "Default")
      (node (ref "IC1") (pin "6") (pinfunction "-IN_6") (pintype "input"))
      (node (ref "R11") (pin "2") (pinfunction "2_2") (pintype "passive"))
      (node (ref "R6") (pin "1") (pinfunction "1_1") (pintype "passive"))
    )
    (net (code "14") (name "Net-(IC1B-OUT)") (class "Default")
      (node (ref "IC1") (pin "7") (pinfunction "OUT_7") (pintype "output"))
      (node (ref "IC2") (pin "1") (pinfunction "+IN_1") (pintype "input"))
      (node (ref "R11") (pin "1") (pinfunction "1_1") (pintype "passive"))
      (node (ref "R12") (pin "2") (pinfunction "2_2") (pintype "passive"))
    )
    (net (code "15") (name "Net-(IC1C--IN)") (class "Default")
      (node (ref "IC1") (pin "9") (pinfunction "-IN_9") (pintype "input"))
      (node (ref "R5") (pin "1") (pinfunction "1_1") (pintype "passive"))
      (node (ref "R7") (pin "2") (pinfunction "2_2") (pintype "passive"))
      (node (ref "R8") (pin "1") (pinfunction "1_1") (pintype "passive"))
      (node (ref "R9") (pin "1") (pinfunction "1_1") (pintype "passive"))
    )
    (net (code "16") (name "Net-(IC1C-OUT)") (class "Default")
      (node (ref "IC1") (pin "8") (pinfunction "OUT_8") (pintype "output"))
      (node (ref "R13") (pin "2") (pinfunction "2_2") (pintype "passive"))
      (node (ref "R7") (pin "1") (pinfunction "1_1") (pintype "passive"))
    )
    (net (code "17") (name "Net-(IC1D--IN)") (class "Default")
      (node (ref "IC1") (pin "13") (pinfunction "-IN_13") (pintype "input"))
      (node (ref "R1") (pin "2") (pinfunction "2_2") (pintype "passive"))
      (node (ref "R4") (pin "1") (pinfunction "1_1") (pintype "passive"))
    )
    (net (code "18") (name "Net-(IC1D-OUT)") (class "Default")
      (node (ref "IC1") (pin "14") (pinfunction "OUT_14") (pintype "output"))
      (node (ref "R1") (pin "1") (pinfunction "1_1") (pintype "passive"))
      (node (ref "R14") (pin "2") (pinfunction "2_2") (pintype "passive"))
    )
    (net (code "19") (name "Net-(IC2--IN)") (class "Default")
      (node (ref "IC2") (pin "3") (pinfunction "-IN_3") (pintype "input"))
      (node (ref "LED1") (pin "K") (pinfunction "C_K") (pintype "passive"))
      (node (ref "R10") (pin "1") (pinfunction "1_1") (pintype "passive"))
    )
    (net (code "20") (name "Net-(IC2-OUT)") (class "Default")
      (node (ref "IC2") (pin "4") (pinfunction "OUT_4") (pintype "output"))
      (node (ref "LED1") (pin "A") (pinfunction "A_A") (pintype "passive"))
    )
    (net (code "21") (name "Net-(IC3A-+IN)") (class "Default")
      (node (ref "D7") (pin "A") (pinfunction "A_A") (pintype "passive"))
      (node (ref "D8") (pin "A") (pinfunction "A_A") (pintype "passive"))
      (node (ref "IC3") (pin "3") (pinfunction "+IN_3") (pintype "input"))
      (node (ref "R17") (pin "1") (pinfunction "1_1") (pintype "passive"))
    )
    (net (code "22") (name "Net-(IC3A--IN)") (class "Default")
      (node (ref "D5") (pin "A") (pinfunction "A_A") (pintype "passive"))
      (node (ref "IC3") (pin "2") (pinfunction "-IN_2") (pintype "input"))
      (node (ref "R15") (pin "1") (pinfunction "1_1") (pintype "passive"))
    )
    (net (code "23") (name "Net-(IC3A-OUT)") (class "Default")
      (node (ref "D5") (pin "C") (pinfunction "C_C") (pintype "passive"))
      (node (ref "IC3") (pin "1") (pinfunction "OUT_1") (pintype "output"))
      (node (ref "R23") (pin "2") (pinfunction "2_2") (pintype "passive"))
    )
    (net (code "24") (name "Net-(IC3B--IN)") (class "Default")
      (node (ref "IC3") (pin "6") (pinfunction "-IN_6") (pintype "input"))
      (node (ref "IC3") (pin "7") (pinfunction "OUT_7") (pintype "output"))
    )
    (net (code "25") (name "Net-(IC3C-+IN)") (class "Default")
      (node (ref "IC3") (pin "10") (pinfunction "+IN_10") (pintype "input"))
      (node (ref "R20") (pin "1") (pinfunction "1_1") (pintype "passive"))
      (node (ref "R21") (pin "1") (pinfunction "1_1") (pintype "passive"))
    )
    (net (code "26") (name "Net-(IC3C--IN)") (class "Default")
      (node (ref "IC3") (pin "9") (pinfunction "-IN_9") (pintype "input"))
      (node (ref "LED2") (pin "A") (pinfunction "A_A") (pintype "passive"))
      (node (ref "R19") (pin "1") (pinfunction "1_1") (pintype "passive"))
    )
    (net (code "27") (name "Net-(IC3C-OUT)") (class "Default")
      (node (ref "IC3") (pin "8") (pinfunction "OUT_8") (pintype "output"))
      (node (ref "LED2") (pin "K") (pinfunction "C_K") (pintype "passive"))
    )
    (net (code "28") (name "Net-(IC3D-+IN)") (class "Default")
      (node (ref "D10") (pin "C") (pinfunction "C_C") (pintype "passive"))
      (node (ref "D9") (pin "C") (pinfunction "C_C") (pintype "passive"))
      (node (ref "IC3") (pin "12") (pinfunction "+IN_12") (pintype "input"))
      (node (ref "R18") (pin "1") (pinfunction "1_1") (pintype "passive"))
    )
    (net (code "29") (name "Net-(IC3D--IN)") (class "Default")
      (node (ref "D6") (pin "C") (pinfunction "C_C") (pintype "passive"))
      (node (ref "IC3") (pin "13") (pinfunction "-IN_13") (pintype "input"))
      (node (ref "R16") (pin "1") (pinfunction "1_1") (pintype "passive"))
    )
    (net (code "30") (name "Net-(IC3D-OUT)") (class "Default")
      (node (ref "D6") (pin "A") (pinfunction "A_A") (pintype "passive"))
      (node (ref "IC3") (pin "14") (pinfunction "OUT_14") (pintype "output"))
      (node (ref "R22") (pin "2") (pinfunction "2_2") (pintype "passive"))
    )
    (net (code "31") (name "Net-(IC4A--IN)") (class "Default")
      (node (ref "IC4") (pin "2") (pinfunction "-IN_2") (pintype "input"))
      (node (ref "R27") (pin "2") (pinfunction "2_2") (pintype "passive"))
      (node (ref "R29") (pin "1") (pinfunction "1_1") (pintype "passive"))
    )
    (net (code "32") (name "Net-(IC4A-OUT)") (class "Default")
      (node (ref "IC4") (pin "1") (pinfunction "OUT_1") (pintype "output"))
      (node (ref "R27") (pin "1") (pinfunction "1_1") (pintype "passive"))
      (node (ref "R34") (pin "2") (pinfunction "2_2") (pintype "passive"))
    )
    (net (code "33") (name "Net-(IC4B-+IN)") (class "Default")
      (node (ref "IC4") (pin "5") (pinfunction "+IN_5") (pintype "input"))
      (node (ref "J9") (pin "P3") (pinfunction "3_P3") (pintype "passive"))
      (node (ref "R37") (pin "1") (pinfunction "1_1") (pintype "passive"))
    )
    (net (code "34") (name "Net-(IC4B--IN)") (class "Default")
      (node (ref "IC4") (pin "6") (pinfunction "-IN_6") (pintype "input"))
      (node (ref "IC4") (pin "7") (pinfunction "OUT_7") (pintype "output"))
      (node (ref "Q3") (pin "1") (pinfunction "D_1") (pintype "passive"))
      (node (ref "R32") (pin "2") (pinfunction "2_2") (pintype "passive"))
    )
    (net (code "35") (name "Net-(IC4C-+IN)") (class "Default")
      (node (ref "C11") (pin "1") (pinfunction "1_1") (pintype "passive"))
      (node (ref "IC4") (pin "10") (pinfunction "+IN_10") (pintype "input"))
      (node (ref "Q3") (pin "2") (pinfunction "S_2") (pintype "passive"))
    )
    (net (code "36") (name "Net-(IC4C--IN)") (class "Default")
      (node (ref "IC4") (pin "8") (pinfunction "OUT_8") (pintype "output"))
      (node (ref "IC4") (pin "9") (pinfunction "-IN_9") (pintype "input"))
      (node (ref "IC5") (pin "1") (pinfunction "+IN_1") (pintype "input"))
      (node (ref "R35") (pin "2") (pinfunction "2_2") (pintype "passive"))
    )
    (net (code "37") (name "Net-(IC4D-+IN)") (class "Default")
      (node (ref "IC4") (pin "12") (pinfunction "+IN_12") (pintype "input"))
      (node (ref "R28") (pin "2") (pinfunction "2_2") (pintype "passive"))
      (node (ref "R30") (pin "2") (pinfunction "2_2") (pintype "passive"))
    )
    (net (code "38") (name "Net-(IC4D--IN)") (class "Default")
      (node (ref "IC4") (pin "13") (pinfunction "-IN_13") (pintype "input"))
      (node (ref "R25") (pin "1") (pinfunction "1_1") (pintype "passive"))
      (node (ref "R26") (pin "2") (pinfunction "2_2") (pintype "passive"))
    )
    (net (code "39") (name "Net-(IC4D-OUT)") (class "Default")
      (node (ref "D11") (pin "C") (pinfunction "C_C") (pintype "passive"))
      (node (ref "IC4") (pin "14") (pinfunction "OUT_14") (pintype "output"))
    )
    (net (code "40") (name "Net-(IC5--IN)") (class "Default")
      (node (ref "IC5") (pin "3") (pinfunction "-IN_3") (pintype "input"))
      (node (ref "LED3") (pin "A") (pinfunction "A_A") (pintype "passive"))
      (node (ref "R31") (pin "1") (pinfunction "1_1") (pintype "passive"))
    )
    (net (code "41") (name "Net-(IC5-OUT)") (class "Default")
      (node (ref "IC5") (pin "4") (pinfunction "OUT_4") (pintype "output"))
      (node (ref "LED3") (pin "K") (pinfunction "C_K") (pintype "passive"))
    )
    (net (code "42") (name "Net-(J1-3)") (class "Default")
      (node (ref "J1") (pin "P3") (pinfunction "3_P3") (pintype "passive"))
      (node (ref "R2") (pin "2") (pinfunction "2_2") (pintype "passive"))
      (node (ref "R6") (pin "2") (pinfunction "2_2") (pintype "passive"))
      (node (ref "R9") (pin "2") (pinfunction "2_2") (pintype "passive"))
    )
    (net (code "43") (name "Net-(J2-3)") (class "Default")
      (node (ref "J2") (pin "P3") (pinfunction "3_P3") (pintype "passive"))
      (node (ref "R12") (pin "1") (pinfunction "1_1") (pintype "passive"))
    )
    (net (code "44") (name "Net-(J3-3)") (class "Default")
      (node (ref "J3") (pin "P3") (pinfunction "3_P3") (pintype "passive"))
      (node (ref "R14") (pin "1") (pinfunction "1_1") (pintype "passive"))
    )
    (net (code "45") (name "Net-(J4-3)") (class "Default")
      (node (ref "J4") (pin "P3") (pinfunction "3_P3") (pintype "passive"))
      (node (ref "R13") (pin "1") (pinfunction "1_1") (pintype "passive"))
    )
    (net (code "46") (name "Net-(J5-3)") (class "Default")
      (node (ref "D10") (pin "A") (pinfunction "A_A") (pintype "passive"))
      (node (ref "D7") (pin "C") (pinfunction "C_C") (pintype "passive"))
      (node (ref "J5") (pin "P3") (pinfunction "3_P3") (pintype "passive"))
      (node (ref "R20") (pin "2") (pinfunction "2_2") (pintype "passive"))
    )
    (net (code "47") (name "Net-(J6-3)") (class "Default")
      (node (ref "D8") (pin "C") (pinfunction "C_C") (pintype "passive"))
      (node (ref "D9") (pin "A") (pinfunction "A_A") (pintype "passive"))
      (node (ref "J6") (pin "P3") (pinfunction "3_P3") (pintype "passive"))
      (node (ref "R21") (pin "2") (pinfunction "2_2") (pintype "passive"))
    )
    (net (code "48") (name "Net-(J7-3)") (class "Default")
      (node (ref "J7") (pin "P3") (pinfunction "3_P3") (pintype "passive"))
      (node (ref "R22") (pin "1") (pinfunction "1_1") (pintype "passive"))
    )
    (net (code "49") (name "Net-(J8-3)") (class "Default")
      (node (ref "J8") (pin "P3") (pinfunction "3_P3") (pintype "passive"))
      (node (ref "R23") (pin "1") (pinfunction "1_1") (pintype "passive"))
    )
    (net (code "50") (name "Net-(J10-3)") (class "Default")
      (node (ref "C12") (pin "1") (pinfunction "1_1") (pintype "passive"))
      (node (ref "J10") (pin "P3") (pinfunction "3_P3") (pintype "passive"))
      (node (ref "R36") (pin "2") (pinfunction "2_2") (pintype "passive"))
    )
    (net (code "51") (name "Net-(J11-3)") (class "Default")
      (node (ref "J11") (pin "P3") (pinfunction "3_P3") (pintype "passive"))
      (node (ref "J9") (pin "P2") (pinfunction "2_P2") (pintype "passive"))
      (node (ref "R34") (pin "1") (pinfunction "1_1") (pintype "passive"))
    )
    (net (code "52") (name "Net-(J12-3)") (class "Default")
      (node (ref "J12") (pin "P3") (pinfunction "3_P3") (pintype "passive"))
      (node (ref "R35") (pin "1") (pinfunction "1_1") (pintype "passive"))
    )
    (net (code "53") (name "Net-(Q1-PadB)") (class "Default")
      (node (ref "Q1") (pin "B") (pinfunction "B_B") (pintype "passive"))
      (node (ref "Q2") (pin "B") (pinfunction "B_B") (pintype "passive"))
    )
    (net (code "54") (name "Net-(Q3-G)") (class "Default")
      (node (ref "D11") (pin "A") (pinfunction "A_A") (pintype "passive"))
      (node (ref "Q3") (pin "3") (pinfunction "G_3") (pintype "passive"))
      (node (ref "R32") (pin "1") (pinfunction "1_1") (pintype "passive"))
    )
    (net (code "55") (name "VCC") (class "Default")
      (node (ref "C2") (pin "1") (pinfunction "1_1") (pintype "passive"))
      (node (ref "C3") (pin "1") (pinfunction "1_1") (pintype "passive"))
      (node (ref "C6") (pin "1") (pinfunction "1_1") (pintype "passive"))
      (node (ref "C7") (pin "1") (pinfunction "1_1") (pintype "passive"))
      (node (ref "C9") (pin "1") (pinfunction "1_1") (pintype "passive"))
      (node (ref "IC1") (pin "4") (pinfunction "V+_4") (pintype "power_in"))
      (node (ref "IC2") (pin "5") (pinfunction "V+_5") (pintype "power_in"))
      (node (ref "IC3") (pin "4") (pinfunction "V+_4") (pintype "power_in"))
      (node (ref "IC4") (pin "4") (pinfunction "V+_4") (pintype "power_in"))
      (node (ref "IC5") (pin "5") (pinfunction "V+_5") (pintype "power_in"))
      (node (ref "L2") (pin "1") (pinfunction "1_1") (pintype "passive"))
      (node (ref "R15") (pin "2") (pinfunction "2_2") (pintype "passive"))
      (node (ref "R17") (pin "2") (pinfunction "2_2") (pintype "passive"))
      (node (ref "R24") (pin "2") (pinfunction "2_2") (pintype "passive"))
      (node (ref "R25") (pin "2") (pinfunction "2_2") (pintype "passive"))
      (node (ref "R33") (pin "1") (pinfunction "1_1") (pintype "passive"))
    )
    (net (code "56") (name "VEE") (class "Default")
      (node (ref "C1") (pin "2") (pinfunction "2_2") (pintype "passive"))
      (node (ref "C4") (pin "2") (pinfunction "2_2") (pintype "passive"))
      (node (ref "C5") (pin "2") (pinfunction "2_2") (pintype "passive"))
      (node (ref "C8") (pin "2") (pinfunction "2_2") (pintype "passive"))
      (node (ref "IC1") (pin "11") (pinfunction "V-_11") (pintype "power_in"))
      (node (ref "IC2") (pin "2") (pinfunction "V-_2") (pintype "power_in"))
      (node (ref "IC3") (pin "11") (pinfunction "V-_11") (pintype "power_in"))
      (node (ref "IC4") (pin "11") (pinfunction "V-_11") (pintype "power_in"))
      (node (ref "IC5") (pin "2") (pinfunction "V-_2") (pintype "power_in"))
      (node (ref "L1") (pin "1") (pinfunction "1_1") (pintype "passive"))
      (node (ref "R16") (pin "2") (pinfunction "2_2") (pintype "passive"))
      (node (ref "R18") (pin "2") (pinfunction "2_2") (pintype "passive"))
    )
    (net (code "57") (name "unconnected-(J2-2-PadP2)") (class "Default")
      (node (ref "J2") (pin "P2") (pinfunction "2_P2") (pintype "passive"))
    )
    (net (code "58") (name "unconnected-(J3-2-PadP2)") (class "Default")
      (node (ref "J3") (pin "P2") (pinfunction "2_P2") (pintype "passive"))
    )
    (net (code "59") (name "unconnected-(J4-2-PadP2)") (class "Default")
      (node (ref "J4") (pin "P2") (pinfunction "2_P2") (pintype "passive"))
    )
    (net (code "60") (name "unconnected-(J7-2-PadP2)") (class "Default")
      (node (ref "J7") (pin "P2") (pinfunction "2_P2") (pintype "passive"))
    )
    (net (code "61") (name "unconnected-(J8-2-PadP2)") (class "Default")
      (node (ref "J8") (pin "P2") (pinfunction "2_P2") (pintype "passive"))
    )
    (net (code "62") (name "unconnected-(J11-2-PadP2)") (class "Default")
      (node (ref "J11") (pin "P2") (pinfunction "2_P2") (pintype "passive"))
    )
    (net (code "63") (name "unconnected-(J12-2-PadP2)") (class "Default")
      (node (ref "J12") (pin "P2") (pinfunction "2_P2") (pintype "passive"))
    )
    (net (code "64") (name "unconnected-(Q2-PadC)") (class "Default")
      (node (ref "Q2") (pin "C") (pinfunction "C_C") (pintype "passive"))
    )
  )
)
